# ElektroClub2025FLL_V2_schem.net
KiCad netlist of a schematic drawn in EasyEDA
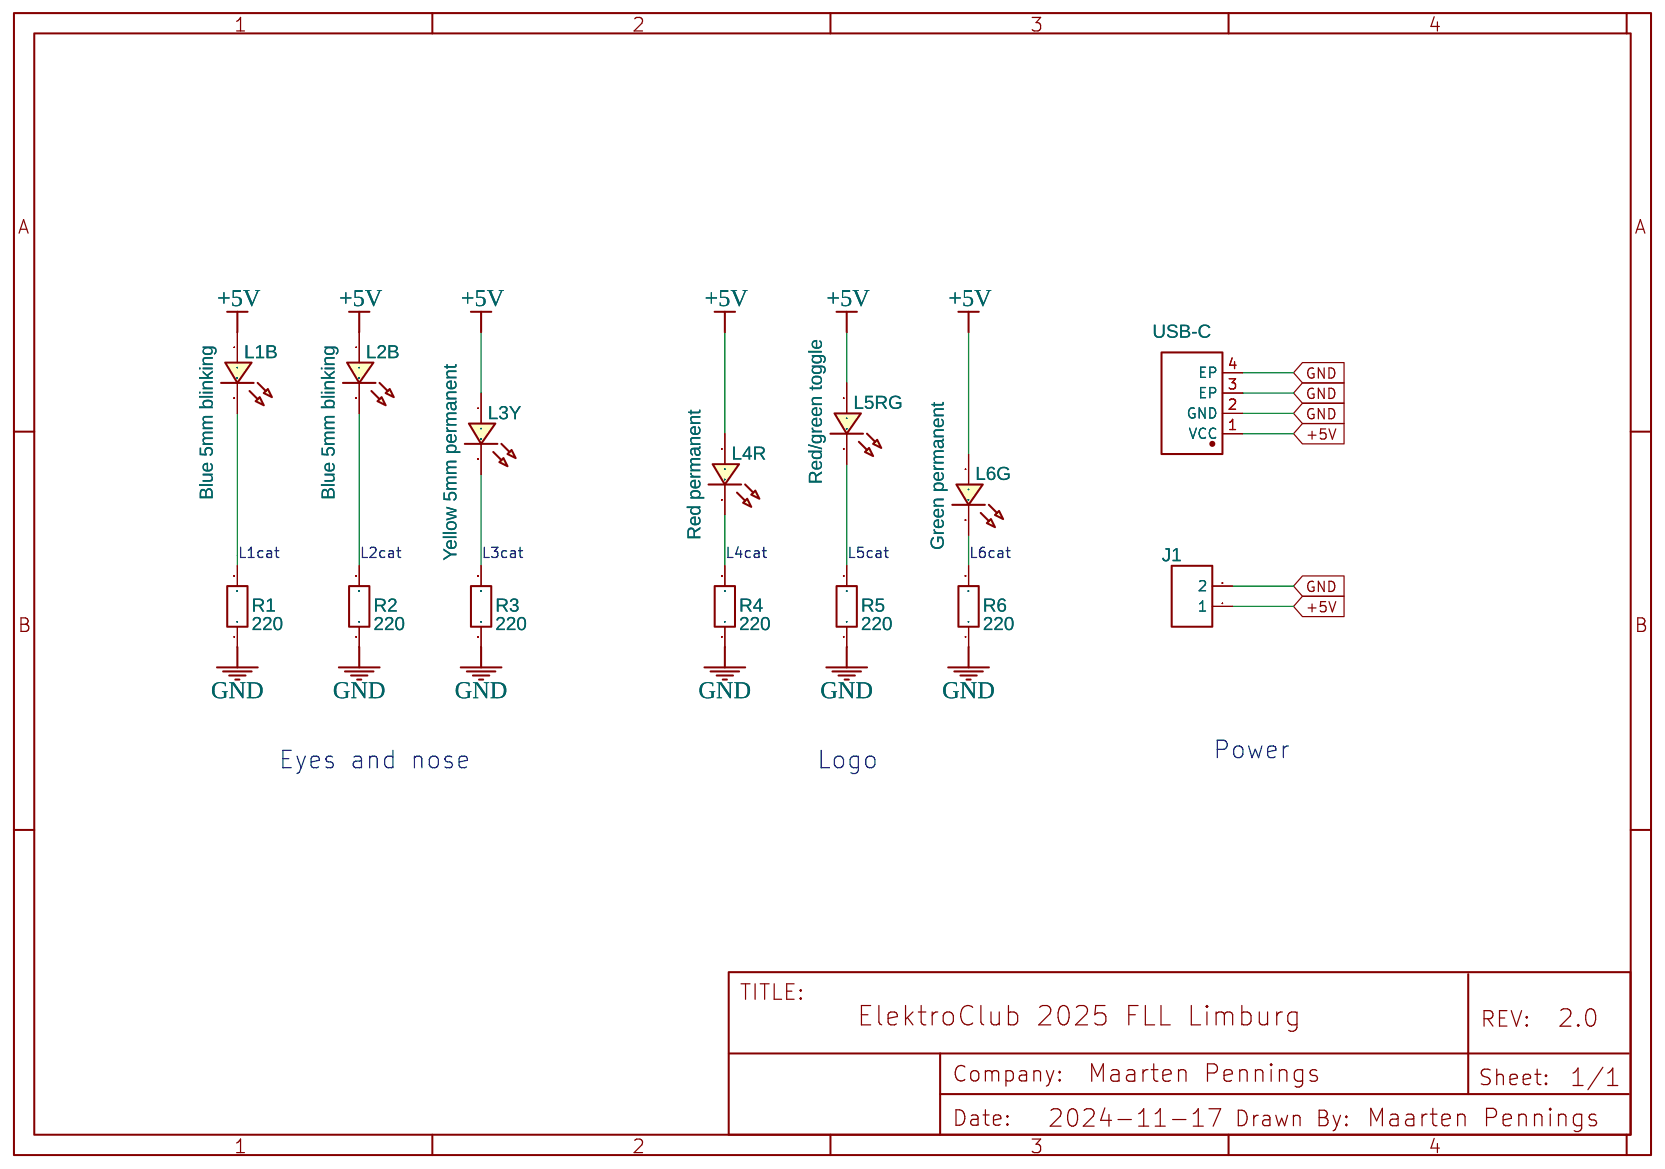
[diagram p0: schematic sheet]

(export (version "E")
  (design (tool "Eeschema 10.0.6"))
  (components
    (comp (ref "J1") (value "HDR-M-2.54_1x2") (libsource (lib "") (part "HDR-M-2.54_1x2")))
    (comp (ref "L1B")
      (value "Blue 5mm blinking")
      (fields
        (field (name "Manufacturer Part") "333-2SYGD/S530-E2")
        (field (name "Manufacturer") "EVERLIGHT(台湾亿光)")
      )
      (libsource (lib "") (part "LED-TH-5mm_G_2"))
    )
    (comp (ref "L2B")
      (value "Blue 5mm blinking")
      (fields
        (field (name "Manufacturer Part") "333-2SYGD/S530-E2")
        (field (name "Manufacturer") "EVERLIGHT(台湾亿光)")
      )
      (libsource (lib "") (part "LED-TH-5mm_G_1"))
    )
    (comp (ref "L3Y")
      (value "Yellow 5mm permanent")
      (fields
        (field (name "Manufacturer Part") "333-2SYGD/S530-E2")
        (field (name "Manufacturer") "EVERLIGHT(台湾亿光)")
      )
      (libsource (lib "") (part "LED-TH-5mm_G"))
    )
    (comp (ref "L4R")
      (value "Red permanent")
      (fields
        (field (name "Manufacturer Part") "333-2SURD/S530-A3")
        (field (name "Manufacturer") "EVERLIGHT(台湾亿光)")
      )
      (libsource (lib "") (part "LED-TH-5mm_R"))
    )
    (comp (ref "L5RG") (value "Red/green toggle") (libsource (lib "") (part "LED-TH-5mm_B")))
    (comp (ref "L6G") (value "Green permanent") (libsource (lib "") (part "LED-TH-5mm_B_1")))
    (comp (ref "R1") (value "220") (libsource (lib "") (part "R_AXIAL-0.4_EU")))
    (comp (ref "R2") (value "220") (libsource (lib "") (part "R_AXIAL-0.4_EU")))
    (comp (ref "R3") (value "220") (libsource (lib "") (part "R_AXIAL-0.4_EU")))
    (comp (ref "R4") (value "220") (libsource (lib "") (part "R_AXIAL-0.4_EU")))
    (comp (ref "R5") (value "220") (libsource (lib "") (part "R_AXIAL-0.4_EU")))
    (comp (ref "R6") (value "220") (libsource (lib "") (part "R_AXIAL-0.4_EU")))
    (comp (ref "USB-C")
      (value "KH-TYPE-C-2P")
      (fields (field (name "Manufacturer") "kinghelm(金航标)"))
      (libsource (lib "") (part "KH-TYPE-C-2P"))
    )
  )
  (nets
    (net (code "1") (name "+5V") (class "Default")
      (node (ref "J1") (pin "1") (pinfunction "1_1") (pintype "unspecified"))
      (node (ref "L1B") (pin "1") (pinfunction "1_1") (pintype "unspecified"))
      (node (ref "L2B") (pin "1") (pinfunction "1_1") (pintype "unspecified"))
      (node (ref "L3Y") (pin "1") (pinfunction "1_1") (pintype "unspecified"))
      (node (ref "L4R") (pin "1") (pinfunction "1_1") (pintype "unspecified"))
      (node (ref "L5RG") (pin "1") (pinfunction "1_1") (pintype "unspecified"))
      (node (ref "L6G") (pin "1") (pinfunction "1_1") (pintype "unspecified"))
      (node (ref "USB-C") (pin "1") (pinfunction "VCC_1") (pintype "unspecified"))
    )
    (net (code "2") (name "/L1cat") (class "Default")
      (node (ref "L1B") (pin "2") (pinfunction "2_2") (pintype "unspecified"))
      (node (ref "R1") (pin "2") (pinfunction "2_2") (pintype "unspecified"))
    )
    (net (code "3") (name "/L2cat") (class "Default")
      (node (ref "L2B") (pin "2") (pinfunction "2_2") (pintype "unspecified"))
      (node (ref "R2") (pin "2") (pinfunction "2_2") (pintype "unspecified"))
    )
    (net (code "4") (name "/L3cat") (class "Default")
      (node (ref "L3Y") (pin "2") (pinfunction "2_2") (pintype "unspecified"))
      (node (ref "R3") (pin "2") (pinfunction "2_2") (pintype "unspecified"))
    )
    (net (code "5") (name "/L4cat") (class "Default")
      (node (ref "L4R") (pin "2") (pinfunction "2_2") (pintype "unspecified"))
      (node (ref "R4") (pin "2") (pinfunction "2_2") (pintype "unspecified"))
    )
    (net (code "6") (name "/L5cat") (class "Default")
      (node (ref "L5RG") (pin "2") (pinfunction "2_2") (pintype "unspecified"))
      (node (ref "R5") (pin "2") (pinfunction "2_2") (pintype "unspecified"))
    )
    (net (code "7") (name "/L6cat") (class "Default")
      (node (ref "L6G") (pin "2") (pinfunction "2_2") (pintype "unspecified"))
      (node (ref "R6") (pin "2") (pinfunction "2_2") (pintype "unspecified"))
    )
    (net (code "8") (name "GND") (class "Default")
      (node (ref "J1") (pin "2") (pinfunction "2_2") (pintype "unspecified"))
      (node (ref "R1") (pin "1") (pinfunction "1_1") (pintype "unspecified"))
      (node (ref "R2") (pin "1") (pinfunction "1_1") (pintype "unspecified"))
      (node (ref "R3") (pin "1") (pinfunction "1_1") (pintype "unspecified"))
      (node (ref "R4") (pin "1") (pinfunction "1_1") (pintype "unspecified"))
      (node (ref "R5") (pin "1") (pinfunction "1_1") (pintype "unspecified"))
      (node (ref "R6") (pin "1") (pinfunction "1_1") (pintype "unspecified"))
      (node (ref "USB-C") (pin "2") (pinfunction "GND_2") (pintype "unspecified"))
      (node (ref "USB-C") (pin "3") (pinfunction "EP_3") (pintype "unspecified"))
      (node (ref "USB-C") (pin "4") (pinfunction "EP_4") (pintype "unspecified"))
    )
  )
)
